# 400ETB.net
KiCad netlist of a schematic drawn in Altium Designer
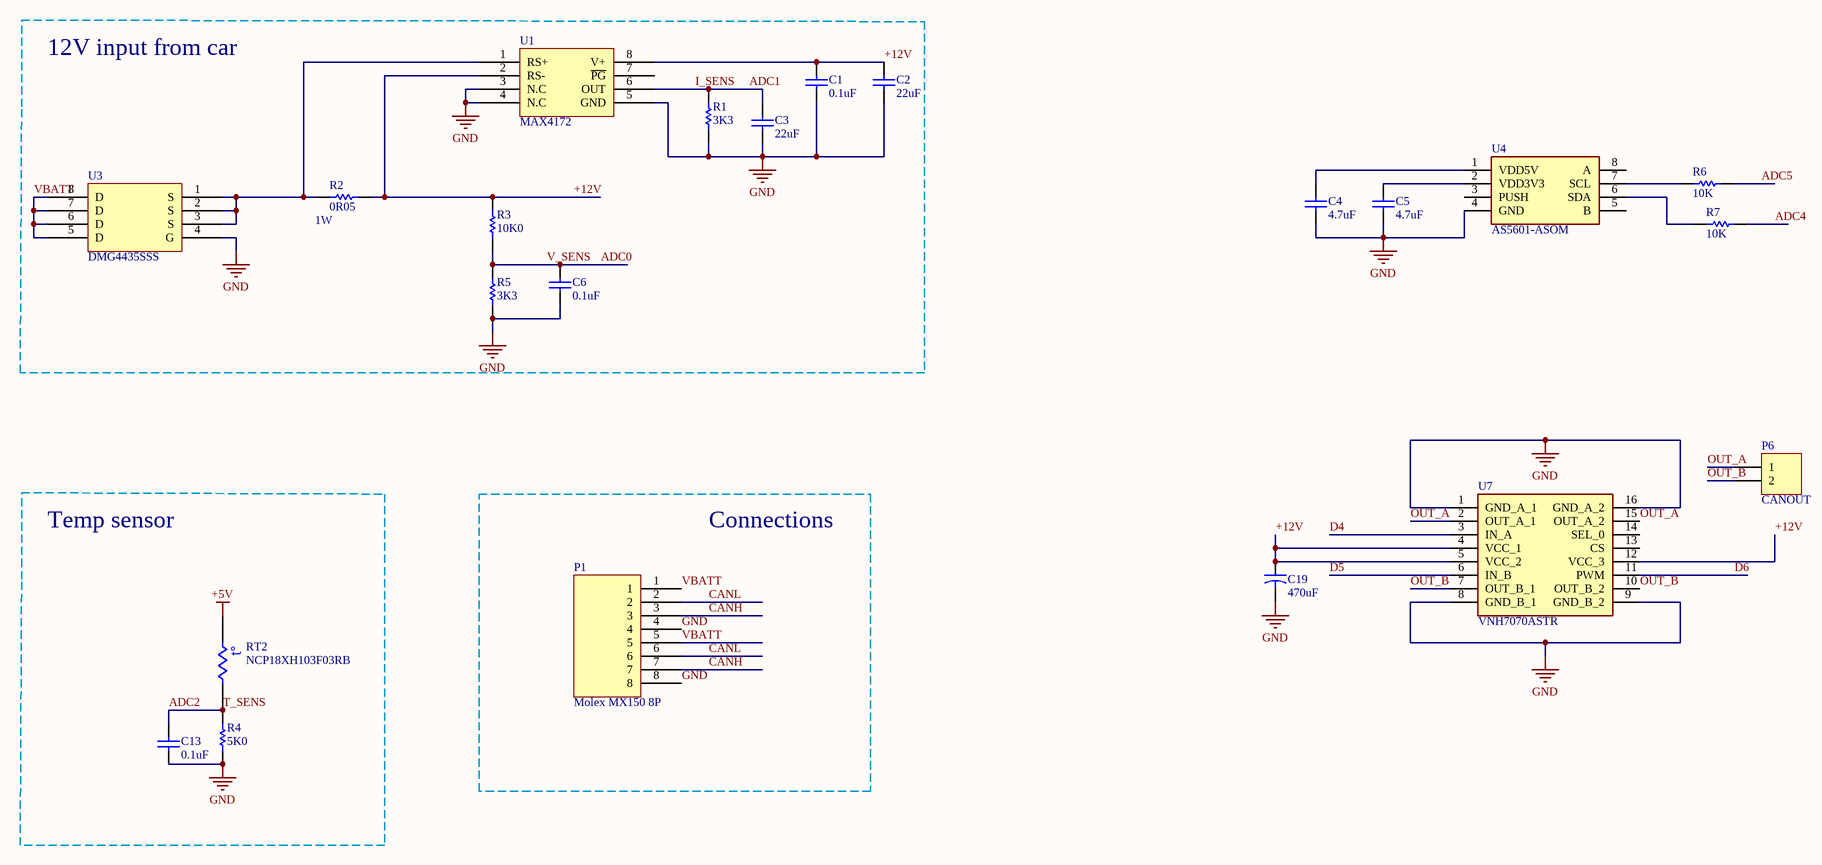
[diagram p0: 400ETB.SchDoc]

(export (version "E")
  (design (tool "Eeschema 10.0.6"))
  (components
    (comp (ref "C1")
      (value "0.1uF")
      (footprint "C0603")
      (description "Capacitor")
      (fields (field (name "PUBLISHER") "Altium Limited"))
      (libsource (lib "Miscellaneous Devices") (part "Cap"))
    )
    (comp (ref "C2")
      (value "22uF")
      (footprint "C1206")
      (description "Capacitor")
      (fields (field (name "PUBLISHER") "Altium Limited"))
      (libsource (lib "Miscellaneous Devices") (part "Cap"))
    )
    (comp (ref "C3")
      (value "22uF")
      (footprint "C1206")
      (description "Capacitor")
      (fields (field (name "PUBLISHER") "Altium Limited"))
      (libsource (lib "Miscellaneous Devices") (part "Cap"))
    )
    (comp (ref "C4")
      (value "4.7uF")
      (footprint "CAPC3216X170N")
      (description "Capacitor (Semiconductor SIM Model)")
      (fields
        (field (name "MANUFACTURER") "Murata")
        (field (name "MANUFACTURER PART NUMBER") "GRM31MR71H105KA88L")
        (field (name "PUBLISHER") "Altium Limited")
      )
      (libsource (lib "Candunio") (part "Cap Semi"))
    )
    (comp (ref "C5")
      (value "4.7uF")
      (footprint "CAPC3216X170N")
      (description "Capacitor (Semiconductor SIM Model)")
      (fields
        (field (name "MANUFACTURER") "Murata")
        (field (name "MANUFACTURER PART NUMBER") "GRM31MR71H105KA88L")
        (field (name "PUBLISHER") "Altium Limited")
      )
      (libsource (lib "Candunio") (part "Cap Semi"))
    )
    (comp (ref "C6")
      (value "0.1uF")
      (footprint "C0603")
      (description "Capacitor")
      (fields (field (name "PUBLISHER") "Altium Limited"))
      (libsource (lib "Miscellaneous Devices") (part "Cap"))
    )
    (comp (ref "C13")
      (value "0.1uF")
      (footprint "C0603")
      (description "Capacitor")
      (fields (field (name "PUBLISHER") "Altium Limited"))
      (libsource (lib "Miscellaneous Devices") (part "Cap"))
    )
    (comp (ref "C19")
      (value "470uF")
      (footprint "CAP THRU 10MM")
      (description "Capacitor")
      (fields (field (name "PUBLISHER") "Altium Limited"))
      (libsource (lib "Miscellaneous Devices") (part "Cap2"))
    )
    (comp (ref "P1")
      (value "Molex MX150 8P")
      (footprint "MX150 8-Pin")
      (libsource (lib "400ETB_SchematicLib") (part "Molex MX150 8P"))
    )
    (comp (ref "P6")
      (value "CANOUT")
      (footprint "Pin Header 1x2 TH Pitch 2.54mm")
      (description "Header, 2-Pin")
      (fields (field (name "PUBLISHER") "Altium Limited"))
      (libsource (lib "Candunio") (part "Header 2"))
    )
    (comp (ref "R1")
      (value "3K3")
      (footprint "R0603")
      (description "Resistor")
      (fields (field (name "PUBLISHER") "Altium Limited"))
      (libsource (lib "Miscellaneous Devices") (part "Res1"))
    )
    (comp (ref "R2")
      (value "0R05")
      (footprint "R1206")
      (description "Resistor")
      (fields (field (name "POWER") "1W") (field (name "PUBLISHER") "Altium Limited"))
      (libsource (lib "Miscellaneous Devices") (part "Res1"))
    )
    (comp (ref "R3")
      (value "10K0")
      (footprint "R0603")
      (description "Resistor")
      (fields (field (name "PUBLISHER") "Altium Limited"))
      (libsource (lib "Miscellaneous Devices") (part "Res1"))
    )
    (comp (ref "R4")
      (value "5K0")
      (footprint "R0603")
      (description "Resistor")
      (fields (field (name "PUBLISHER") "Altium Limited"))
      (libsource (lib "Miscellaneous Devices") (part "Res1"))
    )
    (comp (ref "R5")
      (value "3K3")
      (footprint "R0603")
      (description "Resistor")
      (fields (field (name "PUBLISHER") "Altium Limited"))
      (libsource (lib "Miscellaneous Devices") (part "Res1"))
    )
    (comp (ref "R6")
      (value "10K")
      (footprint "RESC3216X60N")
      (description "Resistor")
      (fields
        (field (name "MANUFACTURER") "Stackpole Electronics")
        (field (name "MANUFACTURER PART NUMBER") "RNCP1206FTD1K00")
      )
      (libsource (lib "Candunio") (part "Res1"))
    )
    (comp (ref "R7")
      (value "10K")
      (footprint "RESC3216X60N")
      (description "Resistor")
      (fields
        (field (name "MANUFACTURER") "Stackpole Electronics")
        (field (name "MANUFACTURER PART NUMBER") "RNCP1206FTD1K00")
      )
      (libsource (lib "Candunio") (part "Res1"))
    )
    (comp (ref "RT2")
      (value "NCP18XH103F03RB")
      (footprint "R0603")
      (description "Thermistor")
      (fields (field (name "PUBLISHER") "Altium Limited"))
      (libsource (lib "Miscellaneous Devices") (part "Res Thermal"))
    )
    (comp (ref "U1")
      (value "MAX4172")
      (footprint "SOIC-8")
      (description "SOIC")
      (libsource (lib "400ETB_SchematicLib") (part "MAX4172"))
    )
    (comp (ref "U3")
      (value "DMG4435SSS")
      (footprint "SOIC-8")
      (description "SOIC")
      (libsource (lib "400ETB_SchematicLib") (part "DMG4435SSS"))
    )
    (comp (ref "U4")
      (value "AS5601-ASOM")
      (footprint "SamacSys:SOIC127P600X175-8N")
      (description "Integrated Circuit")
      (fields
        (field (name "MOUSER PART NUMBER") "985-AS5601-ASOM")
        (field (name "RS PART NUMBER") "1024168P")
      )
      (libsource (lib "*") (part "AS5601-ASOM"))
    )
    (comp (ref "U7")
      (value "VNH7070ASTR")
      (footprint "SamacSys:SOIC127P600X175-16N")
      (description "Integrated Circuit")
      (fields
        (field (name "MOUSER PART NUMBER") "511-VNH7070ASTR")
        (field (name "RS PART NUMBER") "1647017P")
      )
      (libsource (lib "*") (part "VNH7070ASTR"))
    )
  )
  (nets
    (net (code "1") (name "+5V") (class "Default")
      (node (ref "RT2") (pin "1") (pinfunction "1_1") (pintype "passive"))
    )
    (net (code "2") (name "/+12V") (class "Default")
      (node (ref "C1") (pin "2") (pinfunction "2_2") (pintype "passive"))
      (node (ref "C19") (pin "1") (pinfunction "1_1") (pintype "passive"))
      (node (ref "C2") (pin "2") (pinfunction "2_2") (pintype "passive"))
      (node (ref "R2") (pin "2") (pinfunction "2_2") (pintype "passive"))
      (node (ref "R3") (pin "2") (pinfunction "2_2") (pintype "passive"))
      (node (ref "U1") (pin "2") (pinfunction "RS-_2") (pintype "passive"))
      (node (ref "U1") (pin "8") (pinfunction "V+_8") (pintype "passive"))
      (node (ref "U7") (pin "12") (pinfunction "VCC_3_12") (pintype "passive"))
      (node (ref "U7") (pin "4") (pinfunction "VCC_1_4") (pintype "passive"))
      (node (ref "U7") (pin "5") (pinfunction "VCC_2_5") (pintype "passive"))
    )
    (net (code "3") (name "/ADC0") (class "Default")
      (node (ref "C6") (pin "2") (pinfunction "2_2") (pintype "passive"))
      (node (ref "R3") (pin "1") (pinfunction "1_1") (pintype "passive"))
      (node (ref "R5") (pin "2") (pinfunction "2_2") (pintype "passive"))
    )
    (net (code "4") (name "/ADC1") (class "Default")
      (node (ref "C3") (pin "2") (pinfunction "2_2") (pintype "passive"))
      (node (ref "R1") (pin "2") (pinfunction "2_2") (pintype "passive"))
      (node (ref "U1") (pin "6") (pinfunction "OUT_6") (pintype "passive"))
    )
    (net (code "5") (name "/ADC2") (class "Default")
      (node (ref "C13") (pin "2") (pinfunction "2_2") (pintype "passive"))
      (node (ref "R4") (pin "2") (pinfunction "2_2") (pintype "passive"))
      (node (ref "RT2") (pin "2") (pinfunction "2_2") (pintype "passive"))
    )
    (net (code "6") (name "/ADC4") (class "Default")
      (node (ref "R7") (pin "2") (pinfunction "2_2") (pintype "passive"))
    )
    (net (code "7") (name "/ADC5") (class "Default")
      (node (ref "R6") (pin "2") (pinfunction "2_2") (pintype "passive"))
    )
    (net (code "8") (name "/CANH") (class "Default")
      (node (ref "P1") (pin "3") (pinfunction "3_3") (pintype "passive"))
      (node (ref "P1") (pin "7") (pinfunction "7_7") (pintype "passive"))
    )
    (net (code "9") (name "/CANL") (class "Default")
      (node (ref "P1") (pin "2") (pinfunction "2_2") (pintype "passive"))
      (node (ref "P1") (pin "6") (pinfunction "6_6") (pintype "passive"))
    )
    (net (code "10") (name "/D4") (class "Default")
      (node (ref "U7") (pin "3") (pinfunction "IN_A_3") (pintype "passive"))
    )
    (net (code "11") (name "/D5") (class "Default")
      (node (ref "U7") (pin "6") (pinfunction "IN_B_6") (pintype "passive"))
    )
    (net (code "12") (name "/D6") (class "Default")
      (node (ref "U7") (pin "11") (pinfunction "PWM_11") (pintype "passive"))
    )
    (net (code "13") (name "/OUT_A") (class "Default")
      (node (ref "P6") (pin "1") (pinfunction "1_1") (pintype "passive"))
      (node (ref "U7") (pin "15") (pinfunction "OUT_A_2_15") (pintype "passive"))
      (node (ref "U7") (pin "2") (pinfunction "OUT_A_1_2") (pintype "passive"))
    )
    (net (code "14") (name "/OUT_B") (class "Default")
      (node (ref "P6") (pin "2") (pinfunction "2_2") (pintype "passive"))
      (node (ref "U7") (pin "10") (pinfunction "OUT_B_2_10") (pintype "passive"))
      (node (ref "U7") (pin "7") (pinfunction "OUT_B_1_7") (pintype "passive"))
    )
    (net (code "15") (name "/VBATT") (class "Default")
      (node (ref "P1") (pin "1") (pinfunction "1_1") (pintype "passive"))
      (node (ref "P1") (pin "5") (pinfunction "5_5") (pintype "passive"))
      (node (ref "U3") (pin "5") (pinfunction "D_5") (pintype "passive"))
      (node (ref "U3") (pin "6") (pinfunction "D_6") (pintype "passive"))
      (node (ref "U3") (pin "7") (pinfunction "D_7") (pintype "passive"))
      (node (ref "U3") (pin "8") (pinfunction "D_8") (pintype "passive"))
    )
    (net (code "16") (name "GND") (class "Default")
      (node (ref "C1") (pin "1") (pinfunction "1_1") (pintype "passive"))
      (node (ref "C13") (pin "1") (pinfunction "1_1") (pintype "passive"))
      (node (ref "C19") (pin "2") (pinfunction "2_2") (pintype "passive"))
      (node (ref "C2") (pin "1") (pinfunction "1_1") (pintype "passive"))
      (node (ref "C3") (pin "1") (pinfunction "1_1") (pintype "passive"))
      (node (ref "C4") (pin "1") (pinfunction "1_1") (pintype "passive"))
      (node (ref "C5") (pin "1") (pinfunction "1_1") (pintype "passive"))
      (node (ref "C6") (pin "1") (pinfunction "1_1") (pintype "passive"))
      (node (ref "P1") (pin "4") (pinfunction "4_4") (pintype "passive"))
      (node (ref "P1") (pin "8") (pinfunction "8_8") (pintype "passive"))
      (node (ref "R1") (pin "1") (pinfunction "1_1") (pintype "passive"))
      (node (ref "R4") (pin "1") (pinfunction "1_1") (pintype "passive"))
      (node (ref "R5") (pin "1") (pinfunction "1_1") (pintype "passive"))
      (node (ref "U1") (pin "3") (pinfunction "N.C_3") (pintype "passive"))
      (node (ref "U1") (pin "4") (pinfunction "N.C_4") (pintype "passive"))
      (node (ref "U1") (pin "5") (pinfunction "GND_5") (pintype "passive"))
      (node (ref "U3") (pin "4") (pinfunction "G_4") (pintype "passive"))
      (node (ref "U4") (pin "4") (pinfunction "GND_4") (pintype "power_in"))
      (node (ref "U7") (pin "1") (pinfunction "GND_A_1_1") (pintype "passive"))
      (node (ref "U7") (pin "16") (pinfunction "GND_A_2_16") (pintype "passive"))
      (node (ref "U7") (pin "8") (pinfunction "GND_B_1_8") (pintype "passive"))
      (node (ref "U7") (pin "9") (pinfunction "GND_B_2_9") (pintype "passive"))
    )
    (net (code "17") (name "Net-(U1-RS+)") (class "Default")
      (node (ref "R2") (pin "1") (pinfunction "1_1") (pintype "passive"))
      (node (ref "U1") (pin "1") (pinfunction "RS+_1") (pintype "passive"))
      (node (ref "U3") (pin "1") (pinfunction "S_1") (pintype "passive"))
      (node (ref "U3") (pin "2") (pinfunction "S_2") (pintype "passive"))
      (node (ref "U3") (pin "3") (pinfunction "S_3") (pintype "passive"))
    )
    (net (code "18") (name "Net-(U4-SCL)") (class "Default")
      (node (ref "R6") (pin "1") (pinfunction "1_1") (pintype "passive"))
      (node (ref "U4") (pin "7") (pinfunction "SCL_7") (pintype "passive"))
    )
    (net (code "19") (name "Net-(U4-SDA)") (class "Default")
      (node (ref "R7") (pin "1") (pinfunction "1_1") (pintype "passive"))
      (node (ref "U4") (pin "6") (pinfunction "SDA_6") (pintype "passive"))
    )
    (net (code "20") (name "Net-(U4-VDD3V3)") (class "Default")
      (node (ref "C5") (pin "2") (pinfunction "2_2") (pintype "passive"))
      (node (ref "U4") (pin "2") (pinfunction "VDD3V3_2") (pintype "power_in"))
    )
    (net (code "21") (name "Net-(U4-VDD5V)") (class "Default")
      (node (ref "C4") (pin "2") (pinfunction "2_2") (pintype "passive"))
      (node (ref "U4") (pin "1") (pinfunction "VDD5V_1") (pintype "power_in"))
    )
    (net (code "22") (name "unconnected-(U1-~{PG}-Pad7)") (class "Default")
      (node (ref "U1") (pin "7") (pinfunction "~{PG}_7") (pintype "passive"))
    )
    (net (code "23") (name "unconnected-(U4-A-Pad8)") (class "Default")
      (node (ref "U4") (pin "8") (pinfunction "A_8") (pintype "passive"))
    )
    (net (code "24") (name "unconnected-(U4-B-Pad5)") (class "Default")
      (node (ref "U4") (pin "5") (pinfunction "B_5") (pintype "passive"))
    )
    (net (code "25") (name "unconnected-(U4-PUSH-Pad3)") (class "Default")
      (node (ref "U4") (pin "3") (pinfunction "PUSH_3") (pintype "passive"))
    )
    (net (code "26") (name "unconnected-(U7-CS-Pad13)") (class "Default")
      (node (ref "U7") (pin "13") (pinfunction "CS_13") (pintype "passive"))
    )
    (net (code "27") (name "unconnected-(U7-SEL_0-Pad14)") (class "Default")
      (node (ref "U7") (pin "14") (pinfunction "SEL_0_14") (pintype "passive"))
    )
  )
)
